# rf_transmitter_using_jockey_switch.net
KiCad netlist of a schematic drawn in EAGLE
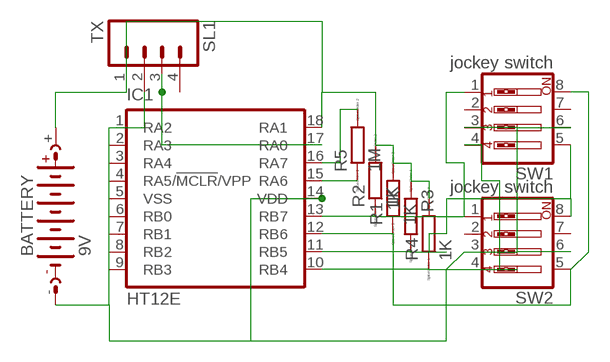
[diagram p0: schematic, sheet 1]

(export (version "E")
  (design (tool "Eeschema 10.0.6"))
  (components
    (comp (ref "BATTERY")
      (value "9V")
      (footprint "eagle-import:AB9V")
      (libsource (lib "eagle-import") (part "AB9V"))
    )
    (comp (ref "IC1")
      (value "HT12E")
      (footprint "eagle-import:DIL18")
      (libsource (lib "eagle-import") (part "PIC16F1826/27P"))
    )
    (comp (ref "R1")
      (value "1K")
      (footprint "eagle-import:0204_7")
      (libsource (lib "eagle-import") (part "R0204/7"))
    )
    (comp (ref "R2")
      (value "1K")
      (footprint "eagle-import:0204_7")
      (libsource (lib "eagle-import") (part "R0204/7"))
    )
    (comp (ref "R3")
      (value "1K")
      (footprint "eagle-import:0204_7")
      (libsource (lib "eagle-import") (part "R0204/7"))
    )
    (comp (ref "R4")
      (value "1K")
      (footprint "eagle-import:0204_7")
      (libsource (lib "eagle-import") (part "R0204/7"))
    )
    (comp (ref "R5")
      (value "1M")
      (footprint "eagle-import:0204_7")
      (libsource (lib "eagle-import") (part "R0204/7"))
    )
    (comp (ref "SL1")
      (value "TX")
      (footprint "eagle-import:04P")
      (libsource (lib "eagle-import") (part "M04"))
    )
    (comp (ref "SW1")
      (value "jockey switch")
      (footprint "eagle-import:EDG-04")
      (libsource (lib "eagle-import") (part "SW_DIP-4"))
    )
    (comp (ref "SW2")
      (value "jockey switch")
      (footprint "eagle-import:EDG-04")
      (libsource (lib "eagle-import") (part "SW_DIP-4"))
    )
  )
  (nets
    (net (code "1") (name "Net-(IC1-RA0)") (class "Default")
      (node (ref "IC1") (pin "17") (pinfunction "RA0_17") (pintype "bidirectional"))
      (node (ref "SL1") (pin "3") (pinfunction "3_3") (pintype "passive"))
    )
    (net (code "2") (name "Net-(IC1-RA1)") (class "Default")
      (node (ref "BATTERY") (pin "+") (pinfunction "+_+") (pintype "passive"))
      (node (ref "IC1") (pin "18") (pinfunction "RA1_18") (pintype "bidirectional"))
      (node (ref "R1") (pin "2") (pinfunction "2_2") (pintype "passive"))
      (node (ref "R2") (pin "2") (pinfunction "2_2") (pintype "passive"))
      (node (ref "R3") (pin "1") (pinfunction "1_1") (pintype "passive"))
      (node (ref "R4") (pin "2") (pinfunction "2_2") (pintype "passive"))
      (node (ref "SL1") (pin "1") (pinfunction "1_1") (pintype "passive"))
    )
    (net (code "3") (name "Net-(IC1-RA2)") (class "Default")
      (node (ref "BATTERY") (pin "-") (pinfunction "-_-") (pintype "passive"))
      (node (ref "IC1") (pin "1") (pinfunction "RA2_1") (pintype "bidirectional"))
      (node (ref "IC1") (pin "14") (pinfunction "VDD_14") (pintype "power_in"))
      (node (ref "IC1") (pin "2") (pinfunction "RA3_2") (pintype "bidirectional"))
      (node (ref "IC1") (pin "3") (pinfunction "RA4_3") (pintype "bidirectional"))
      (node (ref "IC1") (pin "4") (pinfunction "RA5/~{MCLR}/VPP_4") (pintype "bidirectional"))
      (node (ref "IC1") (pin "5") (pinfunction "VSS_5") (pintype "power_in"))
      (node (ref "IC1") (pin "6") (pinfunction "RB0_6") (pintype "bidirectional"))
      (node (ref "IC1") (pin "7") (pinfunction "RB1_7") (pintype "bidirectional"))
      (node (ref "IC1") (pin "8") (pinfunction "RB2_8") (pintype "bidirectional"))
      (node (ref "IC1") (pin "9") (pinfunction "RB3_9") (pintype "bidirectional"))
      (node (ref "SL1") (pin "2") (pinfunction "2_2") (pintype "passive"))
      (node (ref "SW1") (pin "3") (pinfunction "3_3") (pintype "passive"))
      (node (ref "SW1") (pin "6") (pinfunction "6_6") (pintype "passive"))
      (node (ref "SW2") (pin "3") (pinfunction "3_3") (pintype "passive"))
      (node (ref "SW2") (pin "6") (pinfunction "6_6") (pintype "passive"))
    )
    (net (code "4") (name "Net-(IC1-RA6)") (class "Default")
      (node (ref "IC1") (pin "15") (pinfunction "RA6_15") (pintype "bidirectional"))
      (node (ref "R5") (pin "1") (pinfunction "1_1") (pintype "passive"))
    )
    (net (code "5") (name "Net-(IC1-RA7)") (class "Default")
      (node (ref "IC1") (pin "16") (pinfunction "RA7_16") (pintype "bidirectional"))
      (node (ref "R5") (pin "2") (pinfunction "2_2") (pintype "passive"))
    )
    (net (code "6") (name "Net-(IC1-RB4)") (class "Default")
      (node (ref "IC1") (pin "10") (pinfunction "RB4_10") (pintype "bidirectional"))
      (node (ref "R4") (pin "1") (pinfunction "1_1") (pintype "passive"))
      (node (ref "SW1") (pin "4") (pinfunction "4_4") (pintype "passive"))
      (node (ref "SW2") (pin "4") (pinfunction "4_4") (pintype "passive"))
    )
    (net (code "7") (name "Net-(IC1-RB5)") (class "Default")
      (node (ref "IC1") (pin "11") (pinfunction "RB5_11") (pintype "bidirectional"))
      (node (ref "R3") (pin "2") (pinfunction "2_2") (pintype "passive"))
      (node (ref "SW1") (pin "5") (pinfunction "5_5") (pintype "passive"))
      (node (ref "SW2") (pin "8") (pinfunction "8_8") (pintype "passive"))
    )
    (net (code "8") (name "Net-(IC1-RB6)") (class "Default")
      (node (ref "IC1") (pin "12") (pinfunction "RB6_12") (pintype "bidirectional"))
      (node (ref "R1") (pin "1") (pinfunction "1_1") (pintype "passive"))
      (node (ref "SW1") (pin "8") (pinfunction "8_8") (pintype "passive"))
      (node (ref "SW2") (pin "5") (pinfunction "5_5") (pintype "passive"))
    )
    (net (code "9") (name "Net-(IC1-RB7)") (class "Default")
      (node (ref "IC1") (pin "13") (pinfunction "RB7_13") (pintype "bidirectional"))
      (node (ref "R2") (pin "1") (pinfunction "1_1") (pintype "passive"))
      (node (ref "SW1") (pin "1") (pinfunction "1_1") (pintype "passive"))
      (node (ref "SW2") (pin "1") (pinfunction "1_1") (pintype "passive"))
    )
    (net (code "10") (name "unconnected-(SL1-Pad4)") (class "Default")
      (node (ref "SL1") (pin "4") (pinfunction "4_4") (pintype "passive"))
    )
    (net (code "11") (name "unconnected-(SW1-Pad2)") (class "Default")
      (node (ref "SW1") (pin "2") (pinfunction "2_2") (pintype "passive"))
    )
    (net (code "12") (name "unconnected-(SW1-Pad7)") (class "Default")
      (node (ref "SW1") (pin "7") (pinfunction "7_7") (pintype "passive"))
    )
    (net (code "13") (name "unconnected-(SW2-Pad2)") (class "Default")
      (node (ref "SW2") (pin "2") (pinfunction "2_2") (pintype "passive"))
    )
    (net (code "14") (name "unconnected-(SW2-Pad7)") (class "Default")
      (node (ref "SW2") (pin "7") (pinfunction "7_7") (pintype "passive"))
    )
  )
)
